# STM32F103.net
KiCad netlist of a schematic drawn in Altium Designer
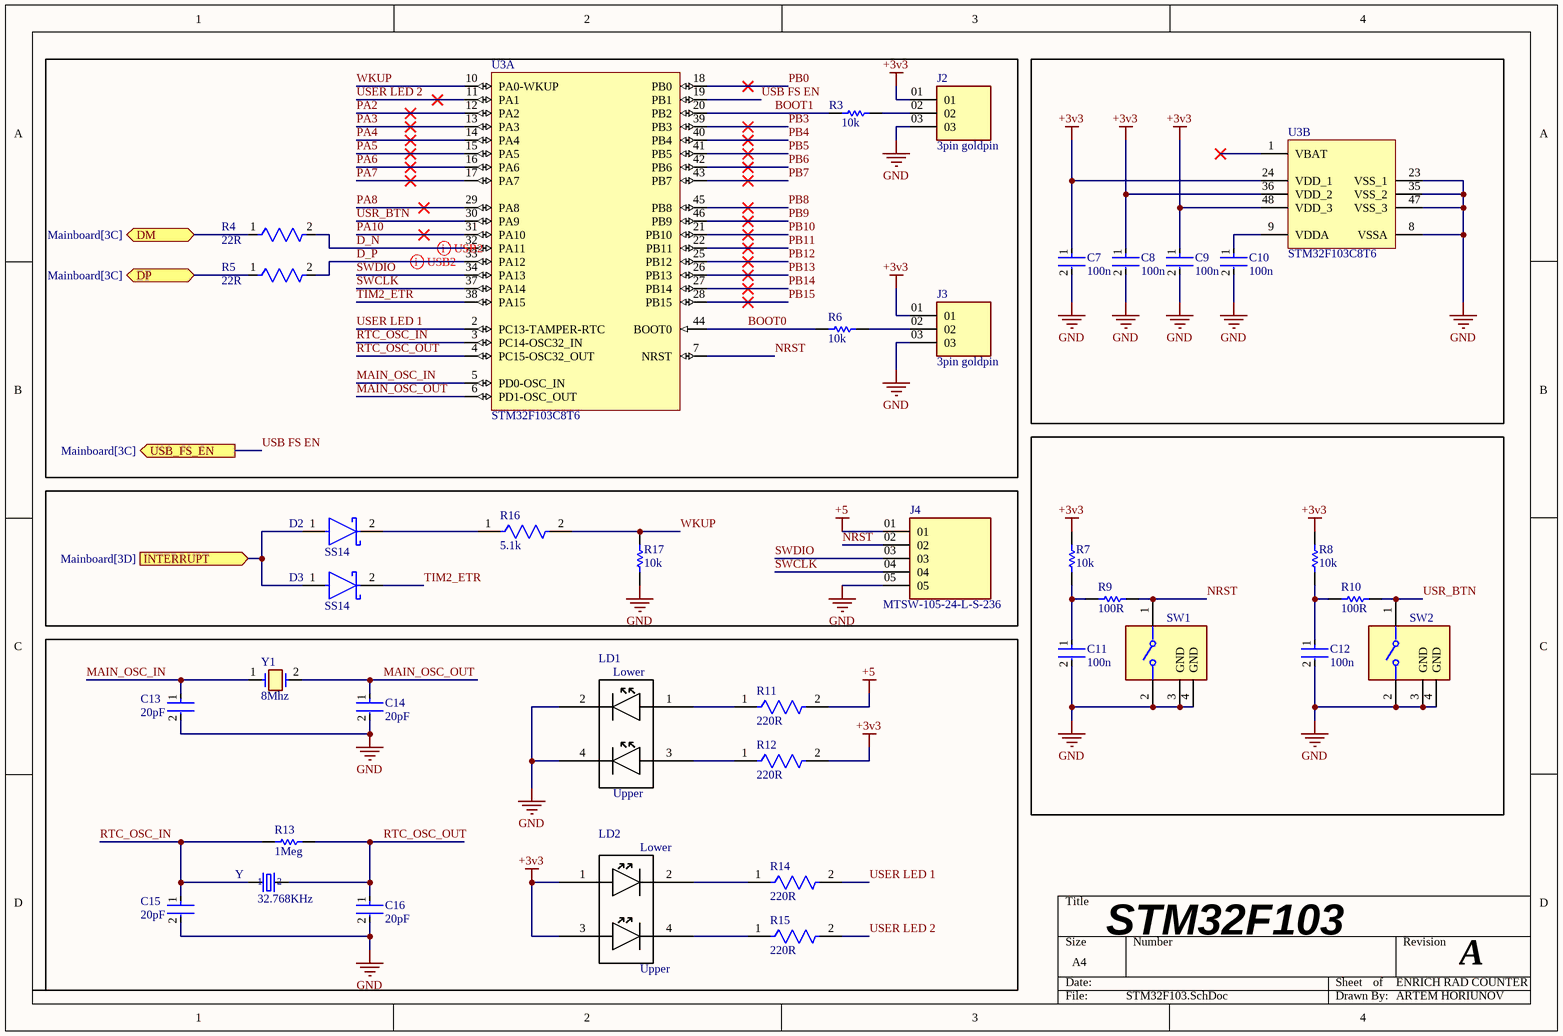
[diagram p0: STM32F103.SchDoc]

(export (version "E")
  (design (tool "Eeschema 10.0.6"))
  (components
    (comp (ref "C7")
      (value "100n")
      (footprint "FP-CGA3E-0_3-0_1-IPC_A")
      (description "Cap Ceramic 100nF 50V X7R 10% Pad SMD 0603 +125°C Automotive T/R")
      (fields (field (name "TOLERANCE") "10%") (field (name "VOLTAGE") "50V"))
      (libsource (lib "Altium Content Vault") (part "b4654b650e69147ec39a6b967a45e02"))
    )
    (comp (ref "C8")
      (value "100n")
      (footprint "FP-CGA3E-0_3-0_1-IPC_A")
      (description "Cap Ceramic 100nF 50V X7R 10% Pad SMD 0603 +125°C Automotive T/R")
      (fields (field (name "TOLERANCE") "10%") (field (name "VOLTAGE") "50V"))
      (libsource (lib "Altium Content Vault") (part "b4654b650e69147ec39a6b967a45e02"))
    )
    (comp (ref "C9")
      (value "100n")
      (footprint "FP-CGA3E-0_3-0_1-IPC_A")
      (description "Cap Ceramic 100nF 50V X7R 10% Pad SMD 0603 +125°C Automotive T/R")
      (fields (field (name "TOLERANCE") "10%") (field (name "VOLTAGE") "50V"))
      (libsource (lib "Altium Content Vault") (part "b4654b650e69147ec39a6b967a45e02"))
    )
    (comp (ref "C10")
      (value "100n")
      (footprint "FP-CGA3E-0_3-0_1-IPC_A")
      (description "Cap Ceramic 100nF 50V X7R 10% Pad SMD 0603 +125°C Automotive T/R")
      (fields (field (name "TOLERANCE") "10%") (field (name "VOLTAGE") "50V"))
      (libsource (lib "Altium Content Vault") (part "b4654b650e69147ec39a6b967a45e02"))
    )
    (comp (ref "C11")
      (value "100n")
      (footprint "FP-C0603C-CF-MFG")
      (description "CAP CER 0.1UF 50V X7R 0603")
      (fields (field (name "TOLERANCE") "0.1") (field (name "MANUFACTURER") "KEMET"))
      (libsource (lib "Altium Content Vault") (part "b4654b650e69147ec39a6b967a45e02"))
    )
    (comp (ref "C12")
      (value "100n")
      (footprint "FP-C0603C-CF-MFG")
      (description "CAP CER 0.1UF 50V X7R 0603")
      (fields (field (name "TOLERANCE") "0.1") (field (name "MANUFACTURER") "KEMET"))
      (libsource (lib "Altium Content Vault") (part "b4654b650e69147ec39a6b967a45e02"))
    )
    (comp (ref "C13")
      (value "20pF")
      (footprint "FP-C0603C-CF-MFG")
      (description "CAP CER 20PF 50V 5% NP0 0603")
      (fields
        (field (name "MANUFACTURER PART NUMBER") "C0603C200J5GACTU")
        (field (name "MANUFACTURER") "KEMET")
      )
      (libsource (lib "Altium Content Vault") (part "b4654b650e69147ec39a6b967a45e02"))
    )
    (comp (ref "C14")
      (value "20pF")
      (footprint "FP-C0603C-CF-MFG")
      (description "CAP CER 20PF 50V 5% NP0 0603")
      (fields
        (field (name "MANUFACTURER PART NUMBER") "C0603C200J5GACTU")
        (field (name "MANUFACTURER") "KEMET")
      )
      (libsource (lib "Altium Content Vault") (part "b4654b650e69147ec39a6b967a45e02"))
    )
    (comp (ref "C15")
      (value "20pF")
      (footprint "FP-C0603C-CF-MFG")
      (description "CAP CER 20PF 50V 5% NP0 0603")
      (fields
        (field (name "MANUFACTURER PART NUMBER") "C0603C200J5GACTU")
        (field (name "MANUFACTURER") "KEMET")
      )
      (libsource (lib "Altium Content Vault") (part "b4654b650e69147ec39a6b967a45e02"))
    )
    (comp (ref "C16")
      (value "20pF")
      (footprint "FP-C0603C-CF-MFG")
      (description "CAP CER 20PF 50V 5% NP0 0603")
      (fields
        (field (name "MANUFACTURER PART NUMBER") "C0603C200J5GACTU")
        (field (name "MANUFACTURER") "KEMET")
      )
      (libsource (lib "Altium Content Vault") (part "b4654b650e69147ec39a6b967a45e02"))
    )
    (comp (ref "D2")
      (value "SS14")
      (footprint "FP-403AE-MFG")
      (description "DIODE SCHOTTKY 40V 1A SMA")
      (fields
        (field (name "MANUFACTURER") "ON Semiconductor")
        (field (name "OCTOPART") "https://octopart.com/ss14-on+semiconductor-29205033")
      )
      (libsource (lib "Altium Content Vault") (part "360ad2f4ac25a952324d13796385471"))
    )
    (comp (ref "D3")
      (value "SS14")
      (footprint "FP-403AE-MFG")
      (description "DIODE SCHOTTKY 40V 1A SMA")
      (fields
        (field (name "MANUFACTURER") "ON Semiconductor")
        (field (name "OCTOPART") "https://octopart.com/ss14-on+semiconductor-29205033")
      )
      (libsource (lib "Altium Content Vault") (part "360ad2f4ac25a952324d13796385471"))
    )
    (comp (ref "J2")
      (value "3pin goldpin")
      (footprint "SAMTEC_HMTSW-103-XX-X-S-XXX")
      (description "Headers & Wire Housings")
      (fields (field (name "MP") "HMTSW-103-13-L-S-100") (field (name "MF") "Samtec"))
      (libsource (lib "HMTSW-103-XX-X-S-XXX") (part "HMTSW-103-XX-X-S-XXX"))
    )
    (comp (ref "J3")
      (value "3pin goldpin")
      (footprint "SAMTEC_HMTSW-103-XX-X-S-XXX")
      (description "Headers & Wire Housings")
      (fields (field (name "MP") "HMTSW-103-13-L-S-100") (field (name "MF") "Samtec"))
      (libsource (lib "HMTSW-103-XX-X-S-XXX") (part "HMTSW-103-XX-X-S-XXX"))
    )
    (comp (ref "J4")
      (value "MTSW-105-24-L-S-236")
      (footprint "SAMTEC_MTSW-105-24-L-S-236")
      (libsource (lib "MTSW-105-24-L-S-236") (part "MTSW-105-24-L-S-236"))
    )
    (comp (ref "LD1")
      (value "~")
      (footprint "LED_HOLDER")
      (libsource (lib "LedHolder") (part "DoubleStack_Side_Led_3mm"))
    )
    (comp (ref "LD2")
      (value "~")
      (footprint "LED_HOLDER")
      (libsource (lib "LedHolder") (part "DoubleStack_Side_Led_3mm"))
    )
    (comp (ref "R3")
      (value "10k")
      (footprint "RESC1609X50X30NL8T20")
      (description "Chip Resistor, 10 KOhm, +/- 1%, 100 mW, -55 to 155 degC, 0603 (1608 Metric), RoHS, Tape and Reel")
      (fields (field (name "MANUFACTURER") "Vishay Semiconductor"))
      (libsource (lib "Altium Content Vault") (part "RES-2"))
    )
    (comp (ref "R4")
      (value "22R")
      (footprint "FP-RC0402-0_4-MFG")
      (fields (field (name "TOLERANCE") "1%"))
      (libsource (lib "Altium Content Vault") (part "RC0402FR-0722RL"))
    )
    (comp (ref "R5")
      (value "22R")
      (footprint "FP-RC0402-0_4-MFG")
      (fields (field (name "TOLERANCE") "1%"))
      (libsource (lib "Altium Content Vault") (part "RC0402FR-0722RL"))
    )
    (comp (ref "R6")
      (value "10k")
      (footprint "RESC1609X50X30NL8T20")
      (description "Chip Resistor, 10 KOhm, +/- 1%, 100 mW, -55 to 155 degC, 0603 (1608 Metric), RoHS, Tape and Reel")
      (fields (field (name "MANUFACTURER") "Vishay Semiconductor"))
      (libsource (lib "Altium Content Vault") (part "RES-2"))
    )
    (comp (ref "R7")
      (value "10k")
      (footprint "RESC0603(1608)_N")
      (description "0.1W 5% 0603 (1608 Metric)  SMD")
      (fields (field (name "TOLERANCE") "5 %") (field (name "POWER") "0.1 W"))
      (libsource (lib "Altium Content Vault") (part "RES"))
    )
    (comp (ref "R8")
      (value "10k")
      (footprint "RESC0603(1608)_N")
      (description "0.1W 5% 0603 (1608 Metric)  SMD")
      (fields (field (name "TOLERANCE") "5 %") (field (name "POWER") "0.1 W"))
      (libsource (lib "Altium Content Vault") (part "RES"))
    )
    (comp (ref "R9")
      (value "100R")
      (footprint "RESC0603(1608)_N")
      (description "0.1W 5% 0603 (1608 Metric)  SMD")
      (fields (field (name "TOLERANCE") "5 %") (field (name "POWER") "0.1 W"))
      (libsource (lib "Altium Content Vault") (part "RES"))
    )
    (comp (ref "R10")
      (value "100R")
      (footprint "RESC0603(1608)_N")
      (description "0.1W 5% 0603 (1608 Metric)  SMD")
      (fields (field (name "TOLERANCE") "5 %") (field (name "POWER") "0.1 W"))
      (libsource (lib "Altium Content Vault") (part "RES"))
    )
    (comp (ref "R11")
      (value "220R")
      (footprint "FP-CRCW0603-HPe3-IPC_A")
      (description "RES Thick Film, 220Ω, 1%, 0.33W, 100ppm/°C, 0603")
      (fields (field (name "TOLERANCE") "1%"))
      (libsource (lib "Altium Content Vault") (part "1029c3af85768c4190bb7ad29bc67b5"))
    )
    (comp (ref "R12")
      (value "220R")
      (footprint "FP-CRCW0603-HPe3-IPC_A")
      (description "RES Thick Film, 220Ω, 1%, 0.33W, 100ppm/°C, 0603")
      (fields (field (name "TOLERANCE") "1%"))
      (libsource (lib "Altium Content Vault") (part "1029c3af85768c4190bb7ad29bc67b5"))
    )
    (comp (ref "R13")
      (value "1Meg")
      (footprint "RESC1608X55X25LL10T15")
      (description "Chip Resistor, 1 MOhm, +/- 1%, 100 mW, -55 to 155 degC, 0603 (1608 Metric), RoHS, Tape and Reel")
      (fields (field (name "TOLERANCE") "20%"))
      (libsource (lib "Altium Content Vault") (part "RES-2"))
    )
    (comp (ref "R14")
      (value "220R")
      (footprint "FP-CRCW0603-HPe3-IPC_A")
      (description "RES Thick Film, 220Ω, 1%, 0.33W, 100ppm/°C, 0603")
      (fields (field (name "TOLERANCE") "1%"))
      (libsource (lib "Altium Content Vault") (part "1029c3af85768c4190bb7ad29bc67b5"))
    )
    (comp (ref "R15")
      (value "220R")
      (footprint "FP-CRCW0603-HPe3-IPC_A")
      (description "RES Thick Film, 220Ω, 1%, 0.33W, 100ppm/°C, 0603")
      (fields (field (name "TOLERANCE") "1%"))
      (libsource (lib "Altium Content Vault") (part "1029c3af85768c4190bb7ad29bc67b5"))
    )
    (comp (ref "R16")
      (value "5.1k")
      (footprint "FP-CRCW0603-e3-IPC_C")
      (description "RES Thick Film, 5.1kΩ, 1%, 0.1W, 100ppm/°C, 0603")
      (fields (field (name "TOLERANCE") "1%"))
      (libsource (lib "Altium Content Vault") (part "1029c3af85768c4190bb7ad29bc67b5"))
    )
    (comp (ref "R17")
      (value "10k")
      (footprint "RESC0603(1608)_N")
      (description "0.1W 5% 0603 (1608 Metric)  SMD")
      (fields (field (name "TOLERANCE") "5 %") (field (name "POWER") "0.1 W"))
      (libsource (lib "Altium Content Vault") (part "RES"))
    )
    (comp (ref "SW1")
      (value "B3F-3122")
      (footprint "FP-B3F-3122-MFG")
      (description "SWITCH TACTILE SPST-NO 0.05A 24V")
      (libsource (lib "Altium Content Vault") (part "05c531d4b500f7e9514fa3f65f375ae"))
    )
    (comp (ref "SW2")
      (value "B3F-3122")
      (footprint "FP-B3F-3122-MFG")
      (description "SWITCH TACTILE SPST-NO 0.05A 24V")
      (libsource (lib "Altium Content Vault") (part "05c531d4b500f7e9514fa3f65f375ae"))
    )
    (comp (ref "U3")
      (value "STM32F103C8T6")
      (footprint "STM-LQFP48_L")
      (libsource (lib "Altium Content Vault") (part "MC-ARM-STM32F103X8_B-SQ48"))
    )
    (comp (ref "Y")
      (value "32.768KHz")
      (footprint "X2-SMD-5.0X3.2X1.3MM")
      (description "32.768KHz quartz")
      (fields (field (name "MF") "Xinhunjing") (field (name "MP") "5032/4P"))
      (libsource (lib "SMD-CRYSTAL-8MHZ-20PF-20PPM_2P-5.0X3.2MM_") (part "SMD-CRYSTAL-8MHZ-20PF-20PPM(2P-5.0X3.2MM)"))
    )
    (comp (ref "Y1")
      (value "8Mhz")
      (footprint "XTAL_NX3215SA-32.768K-STD-MUA-14")
      (description "8MHz quartz")
      (fields (field (name "MP") "NX3215SA-32.768K-STD-MUA-14"))
      (libsource (lib "NX3215SA-32.768K-STD-MUA-14") (part "NX3215SA-32.768K-STD-MUA-14"))
    )
  )
  (nets
    (net (code "1") (name "+3v3") (class "Default")
      (node (ref "C7") (pin "1") (pinfunction "1_1") (pintype "passive"))
      (node (ref "C8") (pin "1") (pinfunction "1_1") (pintype "passive"))
      (node (ref "C9") (pin "1") (pinfunction "1_1") (pintype "passive"))
      (node (ref "J2") (pin "01") (pinfunction "01_01") (pintype "passive"))
      (node (ref "J3") (pin "01") (pinfunction "01_01") (pintype "passive"))
      (node (ref "LD2") (pin "1") (pintype "passive"))
      (node (ref "LD2") (pin "3") (pintype "passive"))
      (node (ref "R12") (pin "2") (pinfunction "2_2") (pintype "passive"))
      (node (ref "R7") (pin "2") (pinfunction "2_2") (pintype "passive"))
      (node (ref "R8") (pin "2") (pinfunction "2_2") (pintype "passive"))
      (node (ref "U3") (pin "24") (pinfunction "VDD_1_24") (pintype "power_in"))
      (node (ref "U3") (pin "36") (pinfunction "VDD_2_36") (pintype "power_in"))
      (node (ref "U3") (pin "48") (pinfunction "VDD_3_48") (pintype "power_in"))
    )
    (net (code "2") (name "+5") (class "Default")
      (node (ref "J4") (pin "01") (pinfunction "01_01") (pintype "passive"))
      (node (ref "R11") (pin "2") (pinfunction "2_2") (pintype "passive"))
    )
    (net (code "3") (name "/BOOT0") (class "Default")
      (node (ref "R6") (pin "1") (pinfunction "1_1") (pintype "passive"))
      (node (ref "U3") (pin "44") (pinfunction "BOOT0_44") (pintype "input"))
    )
    (net (code "4") (name "/BOOT1") (class "Default")
      (node (ref "R3") (pin "1") (pinfunction "1_1") (pintype "passive"))
      (node (ref "U3") (pin "20") (pinfunction "PB2_20") (pintype "bidirectional"))
    )
    (net (code "5") (name "/DM") (class "Default")
      (node (ref "R4") (pin "1") (pinfunction "1_1") (pintype "passive"))
    )
    (net (code "6") (name "/DP") (class "Default")
      (node (ref "R5") (pin "1") (pinfunction "1_1") (pintype "passive"))
    )
    (net (code "7") (name "/D_N") (class "Default")
      (node (ref "R4") (pin "2") (pinfunction "2_2") (pintype "passive"))
      (node (ref "U3") (pin "32") (pinfunction "PA11_32") (pintype "bidirectional"))
    )
    (net (code "8") (name "/D_P") (class "Default")
      (node (ref "R5") (pin "2") (pinfunction "2_2") (pintype "passive"))
      (node (ref "U3") (pin "33") (pinfunction "PA12_33") (pintype "bidirectional"))
    )
    (net (code "9") (name "/INTERRUPT") (class "Default")
      (node (ref "D2") (pin "1") (pinfunction "A_1") (pintype "passive"))
      (node (ref "D3") (pin "1") (pinfunction "A_1") (pintype "passive"))
    )
    (net (code "10") (name "/MAIN_OSC_IN") (class "Default")
      (node (ref "C13") (pin "1") (pinfunction "1_1") (pintype "passive"))
      (node (ref "U3") (pin "5") (pinfunction "PD0-OSC_IN_5") (pintype "bidirectional"))
      (node (ref "Y1") (pin "1") (pinfunction "1_1") (pintype "passive"))
    )
    (net (code "11") (name "/MAIN_OSC_OUT") (class "Default")
      (node (ref "C14") (pin "1") (pinfunction "1_1") (pintype "passive"))
      (node (ref "U3") (pin "6") (pinfunction "PD1-OSC_OUT_6") (pintype "bidirectional"))
      (node (ref "Y1") (pin "2") (pinfunction "2_2") (pintype "passive"))
    )
    (net (code "12") (name "/NRST") (class "Default")
      (node (ref "J4") (pin "02") (pinfunction "02_02") (pintype "passive"))
      (node (ref "R9") (pin "1") (pinfunction "1_1") (pintype "passive"))
      (node (ref "SW1") (pin "1") (pinfunction "1_1") (pintype "passive"))
      (node (ref "U3") (pin "7") (pinfunction "NRST_7") (pintype "bidirectional"))
    )
    (net (code "13") (name "/PA2") (class "Default")
      (node (ref "U3") (pin "12") (pinfunction "PA2_12") (pintype "bidirectional"))
    )
    (net (code "14") (name "/PA3") (class "Default")
      (node (ref "U3") (pin "13") (pinfunction "PA3_13") (pintype "bidirectional"))
    )
    (net (code "15") (name "/PA4") (class "Default")
      (node (ref "U3") (pin "14") (pinfunction "PA4_14") (pintype "bidirectional"))
    )
    (net (code "16") (name "/PA5") (class "Default")
      (node (ref "U3") (pin "15") (pinfunction "PA5_15") (pintype "bidirectional"))
    )
    (net (code "17") (name "/PA6") (class "Default")
      (node (ref "U3") (pin "16") (pinfunction "PA6_16") (pintype "bidirectional"))
    )
    (net (code "18") (name "/PA7") (class "Default")
      (node (ref "U3") (pin "17") (pinfunction "PA7_17") (pintype "bidirectional"))
    )
    (net (code "19") (name "/PA8") (class "Default")
      (node (ref "U3") (pin "29") (pinfunction "PA8_29") (pintype "bidirectional"))
    )
    (net (code "20") (name "/PA10") (class "Default")
      (node (ref "U3") (pin "31") (pinfunction "PA10_31") (pintype "bidirectional"))
    )
    (net (code "21") (name "/PB0") (class "Default")
      (node (ref "U3") (pin "18") (pinfunction "PB0_18") (pintype "bidirectional"))
    )
    (net (code "22") (name "/PB3") (class "Default")
      (node (ref "U3") (pin "39") (pinfunction "PB3_39") (pintype "bidirectional"))
    )
    (net (code "23") (name "/PB4") (class "Default")
      (node (ref "U3") (pin "40") (pinfunction "PB4_40") (pintype "bidirectional"))
    )
    (net (code "24") (name "/PB5") (class "Default")
      (node (ref "U3") (pin "41") (pinfunction "PB5_41") (pintype "bidirectional"))
    )
    (net (code "25") (name "/PB6") (class "Default")
      (node (ref "U3") (pin "42") (pinfunction "PB6_42") (pintype "bidirectional"))
    )
    (net (code "26") (name "/PB7") (class "Default")
      (node (ref "U3") (pin "43") (pinfunction "PB7_43") (pintype "bidirectional"))
    )
    (net (code "27") (name "/PB8") (class "Default")
      (node (ref "U3") (pin "45") (pinfunction "PB8_45") (pintype "bidirectional"))
    )
    (net (code "28") (name "/PB9") (class "Default")
      (node (ref "U3") (pin "46") (pinfunction "PB9_46") (pintype "bidirectional"))
    )
    (net (code "29") (name "/PB10") (class "Default")
      (node (ref "U3") (pin "21") (pinfunction "PB10_21") (pintype "bidirectional"))
    )
    (net (code "30") (name "/PB11") (class "Default")
      (node (ref "U3") (pin "22") (pinfunction "PB11_22") (pintype "bidirectional"))
    )
    (net (code "31") (name "/PB12") (class "Default")
      (node (ref "U3") (pin "25") (pinfunction "PB12_25") (pintype "bidirectional"))
    )
    (net (code "32") (name "/PB13") (class "Default")
      (node (ref "U3") (pin "26") (pinfunction "PB13_26") (pintype "bidirectional"))
    )
    (net (code "33") (name "/PB14") (class "Default")
      (node (ref "U3") (pin "27") (pinfunction "PB14_27") (pintype "bidirectional"))
    )
    (net (code "34") (name "/PB15") (class "Default")
      (node (ref "U3") (pin "28") (pinfunction "PB15_28") (pintype "bidirectional"))
    )
    (net (code "35") (name "/RTC_OSC_IN") (class "Default")
      (node (ref "C15") (pin "1") (pinfunction "1_1") (pintype "passive"))
      (node (ref "R13") (pin "1") (pinfunction "1_1") (pintype "passive"))
      (node (ref "U3") (pin "3") (pinfunction "PC14-OSC32_IN_3") (pintype "bidirectional"))
      (node (ref "Y") (pin "1") (pinfunction "1_1") (pintype "passive"))
    )
    (net (code "36") (name "/RTC_OSC_OUT") (class "Default")
      (node (ref "C16") (pin "1") (pinfunction "1_1") (pintype "passive"))
      (node (ref "R13") (pin "2") (pinfunction "2_2") (pintype "passive"))
      (node (ref "U3") (pin "4") (pinfunction "PC15-OSC32_OUT_4") (pintype "bidirectional"))
      (node (ref "Y") (pin "2") (pinfunction "2_2") (pintype "passive"))
    )
    (net (code "37") (name "/SWCLK") (class "Default")
      (node (ref "J4") (pin "04") (pinfunction "04_04") (pintype "passive"))
      (node (ref "U3") (pin "37") (pinfunction "PA14_37") (pintype "bidirectional"))
    )
    (net (code "38") (name "/SWDIO") (class "Default")
      (node (ref "J4") (pin "03") (pinfunction "03_03") (pintype "passive"))
      (node (ref "U3") (pin "34") (pinfunction "PA13_34") (pintype "bidirectional"))
    )
    (net (code "39") (name "/TIM2_ETR") (class "Default")
      (node (ref "D3") (pin "2") (pinfunction "C_2") (pintype "passive"))
      (node (ref "U3") (pin "38") (pinfunction "PA15_38") (pintype "bidirectional"))
    )
    (net (code "40") (name "/USB FS EN") (class "Default")
      (node (ref "U3") (pin "19") (pinfunction "PB1_19") (pintype "bidirectional"))
    )
    (net (code "41") (name "/USER LED 1") (class "Default")
      (node (ref "R14") (pin "2") (pinfunction "2_2") (pintype "passive"))
      (node (ref "U3") (pin "2") (pinfunction "PC13-TAMPER-RTC_2") (pintype "bidirectional"))
    )
    (net (code "42") (name "/USER LED 2") (class "Default")
      (node (ref "R15") (pin "2") (pinfunction "2_2") (pintype "passive"))
      (node (ref "U3") (pin "11") (pinfunction "PA1_11") (pintype "bidirectional"))
    )
    (net (code "43") (name "/USR_BTN") (class "Default")
      (node (ref "R10") (pin "1") (pinfunction "1_1") (pintype "passive"))
      (node (ref "SW2") (pin "1") (pinfunction "1_1") (pintype "passive"))
      (node (ref "U3") (pin "30") (pinfunction "PA9_30") (pintype "bidirectional"))
    )
    (net (code "44") (name "/WKUP") (class "Default")
      (node (ref "R16") (pin "2") (pinfunction "2_2") (pintype "passive"))
      (node (ref "R17") (pin "2") (pinfunction "2_2") (pintype "passive"))
      (node (ref "U3") (pin "10") (pinfunction "PA0-WKUP_10") (pintype "bidirectional"))
    )
    (net (code "45") (name "GND") (class "Default")
      (node (ref "C10") (pin "2") (pinfunction "2_2") (pintype "passive"))
      (node (ref "C11") (pin "2") (pinfunction "2_2") (pintype "passive"))
      (node (ref "C12") (pin "2") (pinfunction "2_2") (pintype "passive"))
      (node (ref "C13") (pin "2") (pinfunction "2_2") (pintype "passive"))
      (node (ref "C14") (pin "2") (pinfunction "2_2") (pintype "passive"))
      (node (ref "C15") (pin "2") (pinfunction "2_2") (pintype "passive"))
      (node (ref "C16") (pin "2") (pinfunction "2_2") (pintype "passive"))
      (node (ref "C7") (pin "2") (pinfunction "2_2") (pintype "passive"))
      (node (ref "C8") (pin "2") (pinfunction "2_2") (pintype "passive"))
      (node (ref "C9") (pin "2") (pinfunction "2_2") (pintype "passive"))
      (node (ref "J2") (pin "03") (pinfunction "03_03") (pintype "passive"))
      (node (ref "J3") (pin "03") (pinfunction "03_03") (pintype "passive"))
      (node (ref "J4") (pin "05") (pinfunction "05_05") (pintype "passive"))
      (node (ref "LD1") (pin "2") (pintype "passive"))
      (node (ref "LD1") (pin "4") (pintype "passive"))
      (node (ref "R17") (pin "1") (pinfunction "1_1") (pintype "passive"))
      (node (ref "SW1") (pin "2") (pinfunction "2_2") (pintype "passive"))
      (node (ref "SW1") (pin "3") (pinfunction "GND_3") (pintype "power_in"))
      (node (ref "SW1") (pin "4") (pinfunction "GND_4") (pintype "power_in"))
      (node (ref "SW2") (pin "2") (pinfunction "2_2") (pintype "passive"))
      (node (ref "SW2") (pin "3") (pinfunction "GND_3") (pintype "power_in"))
      (node (ref "SW2") (pin "4") (pinfunction "GND_4") (pintype "power_in"))
      (node (ref "U3") (pin "23") (pinfunction "VSS_1_23") (pintype "power_in"))
      (node (ref "U3") (pin "35") (pinfunction "VSS_2_35") (pintype "power_in"))
      (node (ref "U3") (pin "47") (pinfunction "VSS_3_47") (pintype "power_in"))
      (node (ref "U3") (pin "8") (pinfunction "VSSA_8") (pintype "power_in"))
    )
    (net (code "46") (name "Net-(C11-Pad1)") (class "Default")
      (node (ref "C11") (pin "1") (pinfunction "1_1") (pintype "passive"))
      (node (ref "R7") (pin "1") (pinfunction "1_1") (pintype "passive"))
      (node (ref "R9") (pin "2") (pinfunction "2_2") (pintype "passive"))
    )
    (net (code "47") (name "Net-(C12-Pad1)") (class "Default")
      (node (ref "C12") (pin "1") (pinfunction "1_1") (pintype "passive"))
      (node (ref "R10") (pin "2") (pinfunction "2_2") (pintype "passive"))
      (node (ref "R8") (pin "1") (pinfunction "1_1") (pintype "passive"))
    )
    (net (code "48") (name "Net-(D2-C)") (class "Default")
      (node (ref "D2") (pin "2") (pinfunction "C_2") (pintype "passive"))
      (node (ref "R16") (pin "1") (pinfunction "1_1") (pintype "passive"))
    )
    (net (code "49") (name "Net-(J2-Pad02)") (class "Default")
      (node (ref "J2") (pin "02") (pinfunction "02_02") (pintype "passive"))
      (node (ref "R3") (pin "2") (pinfunction "2_2") (pintype "passive"))
    )
    (net (code "50") (name "Net-(J3-Pad02)") (class "Default")
      (node (ref "J3") (pin "02") (pinfunction "02_02") (pintype "passive"))
      (node (ref "R6") (pin "2") (pinfunction "2_2") (pintype "passive"))
    )
    (net (code "51") (name "Net-(LD1-Pad1)") (class "Default")
      (node (ref "LD1") (pin "1") (pintype "passive"))
      (node (ref "R11") (pin "1") (pinfunction "1_1") (pintype "passive"))
    )
    (net (code "52") (name "Net-(LD1-Pad3)") (class "Default")
      (node (ref "LD1") (pin "3") (pintype "passive"))
      (node (ref "R12") (pin "1") (pinfunction "1_1") (pintype "passive"))
    )
    (net (code "53") (name "Net-(LD2-Pad2)") (class "Default")
      (node (ref "LD2") (pin "2") (pintype "passive"))
      (node (ref "R14") (pin "1") (pinfunction "1_1") (pintype "passive"))
    )
    (net (code "54") (name "Net-(LD2-Pad4)") (class "Default")
      (node (ref "LD2") (pin "4") (pintype "passive"))
      (node (ref "R15") (pin "1") (pinfunction "1_1") (pintype "passive"))
    )
    (net (code "55") (name "Net-(U3B-VDDA)") (class "Default")
      (node (ref "C10") (pin "1") (pinfunction "1_1") (pintype "passive"))
      (node (ref "U3") (pin "9") (pinfunction "VDDA_9") (pintype "power_in"))
    )
    (net (code "56") (name "unconnected-(U3B-VBAT-Pad1)") (class "Default")
      (node (ref "U3") (pin "1") (pinfunction "VBAT_1") (pintype "power_in+no_connect"))
    )
  )
)
